# Grove_-_Optical_Rotary_Encoder_TCUT1600X.net
KiCad netlist of a schematic drawn in EAGLE
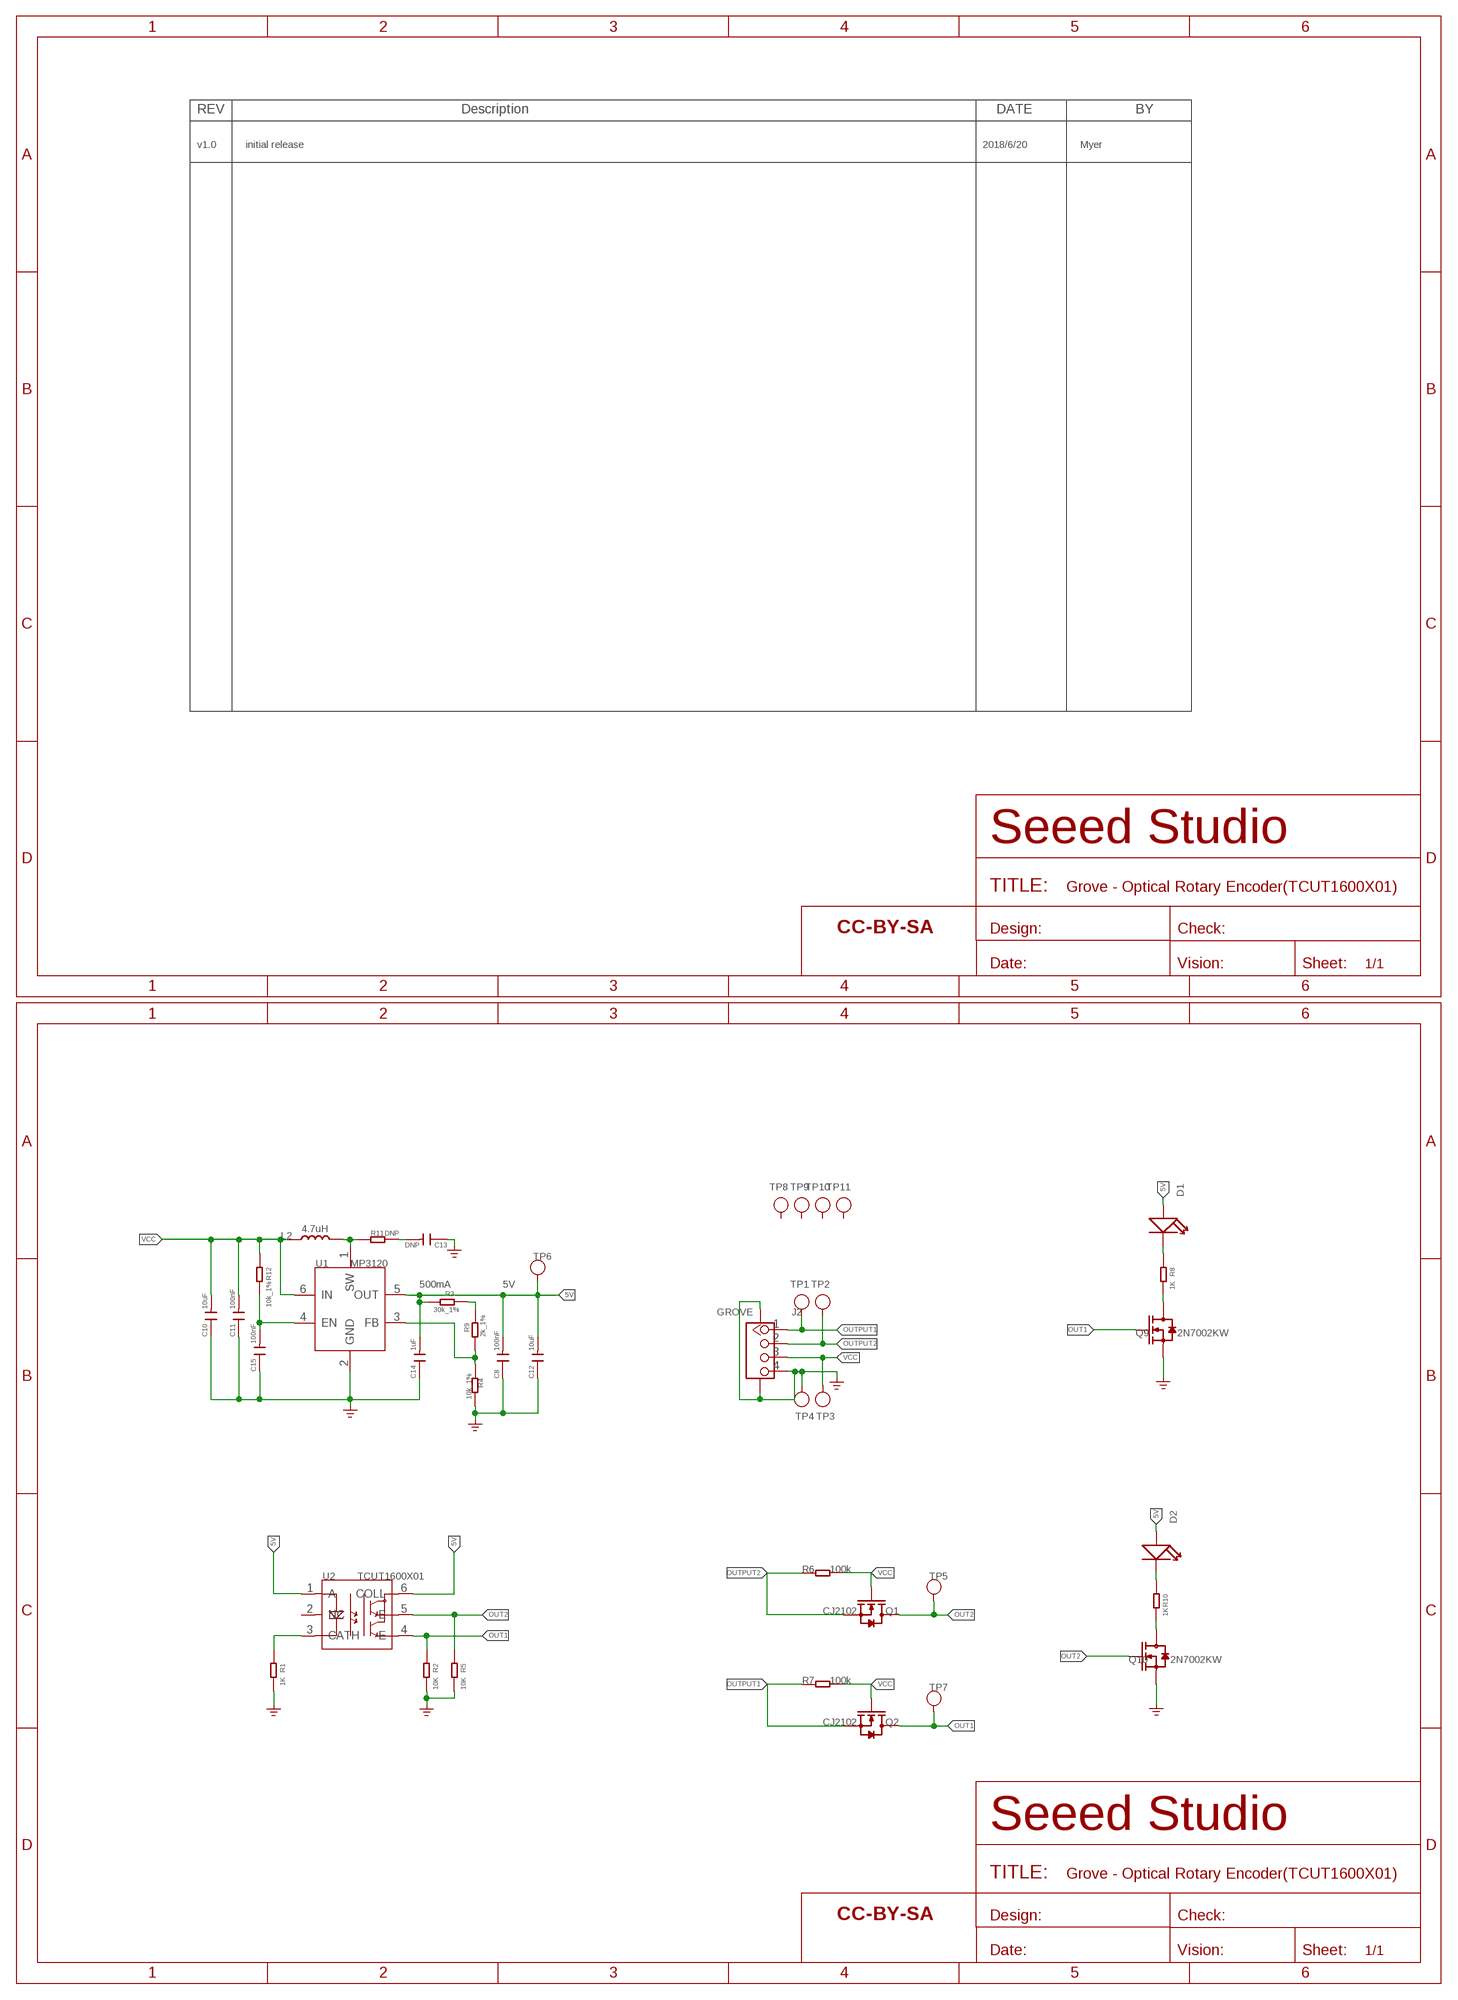
[diagram p0: schematic, sheet 1]

(export (version "E")
  (design (tool "Eeschema 10.0.6"))
  (components
    (comp (ref "C8")
      (value "100nF")
      (footprint "eagle-import:C0603")
      (libsource (lib "eagle-import") (part "C-0603"))
    )
    (comp (ref "C10")
      (value "10uF")
      (footprint "eagle-import:C0603")
      (libsource (lib "eagle-import") (part "C-0603"))
    )
    (comp (ref "C11")
      (value "100nF")
      (footprint "eagle-import:C0603")
      (libsource (lib "eagle-import") (part "C-0603"))
    )
    (comp (ref "C12")
      (value "10uF")
      (footprint "eagle-import:C0603")
      (libsource (lib "eagle-import") (part "C-0603"))
    )
    (comp (ref "C13")
      (value "DNP")
      (footprint "eagle-import:C0603")
      (libsource (lib "eagle-import") (part "C-0603"))
    )
    (comp (ref "C14")
      (value "1uF")
      (footprint "eagle-import:C0603")
      (libsource (lib "eagle-import") (part "C-0603"))
    )
    (comp (ref "C15")
      (value "100nF")
      (footprint "eagle-import:C0603")
      (libsource (lib "eagle-import") (part "C-0603"))
    )
    (comp (ref "D1")
      (value "LED'0603'")
      (footprint "eagle-import:LED-0603")
      (libsource (lib "eagle-import") (part "LED'0603'"))
    )
    (comp (ref "D2")
      (value "LED'0603'")
      (footprint "eagle-import:LED-0603")
      (libsource (lib "eagle-import") (part "LED'0603'"))
    )
    (comp (ref "FR1")
      (value "SEEEDSTUDIO-OPEN-SCH-FRAME")
      (footprint "eagle-import:SEEEDSTUDIO-PCB-FRAME")
      (libsource (lib "eagle-import") (part "SEEEDSTUDIO-OPEN-SCH-FRAME"))
    )
    (comp (ref "J2")
      (value "GROVE")
      (footprint "eagle-import:HW4-SMD-2.0")
      (libsource (lib "eagle-import") (part "GROVE-CONNECTOR-SMD'DD'"))
    )
    (comp (ref "L2")
      (value "4.7uH")
      (footprint "eagle-import:L2016")
      (libsource (lib "eagle-import") (part "LL2016"))
    )
    (comp (ref "Q1")
      (value "CJ2102")
      (footprint "eagle-import:SOT-23@1")
      (libsource (lib "eagle-import") (part "MOSFET-N'SOT23'"))
    )
    (comp (ref "Q2")
      (value "CJ2102")
      (footprint "eagle-import:SOT-23@1")
      (libsource (lib "eagle-import") (part "MOSFET-N'SOT23'"))
    )
    (comp (ref "Q9")
      (value "2N7002KW")
      (footprint "eagle-import:SOT-323")
      (libsource (lib "eagle-import") (part "MOSFET-N+'SI1304BDL'"))
    )
    (comp (ref "Q10")
      (value "2N7002KW")
      (footprint "eagle-import:SOT-323")
      (libsource (lib "eagle-import") (part "MOSFET-N+'SI1304BDL'"))
    )
    (comp (ref "R1")
      (value "1K")
      (footprint "eagle-import:R0603")
      (libsource (lib "eagle-import") (part "R-0603"))
    )
    (comp (ref "R2")
      (value "10K")
      (footprint "eagle-import:R0603")
      (libsource (lib "eagle-import") (part "R-0603"))
    )
    (comp (ref "R3")
      (value "30k_1%")
      (footprint "eagle-import:R0603")
      (libsource (lib "eagle-import") (part "R-0603"))
    )
    (comp (ref "R4")
      (value "10k_1%")
      (footprint "eagle-import:R0603")
      (libsource (lib "eagle-import") (part "R-0603"))
    )
    (comp (ref "R5")
      (value "10K")
      (footprint "eagle-import:R0603")
      (libsource (lib "eagle-import") (part "R-0603"))
    )
    (comp (ref "R6")
      (value "100k")
      (footprint "eagle-import:R0603")
      (libsource (lib "eagle-import") (part "R-0603"))
    )
    (comp (ref "R7")
      (value "100k")
      (footprint "eagle-import:R0603")
      (libsource (lib "eagle-import") (part "R-0603"))
    )
    (comp (ref "R8")
      (value "1K")
      (footprint "eagle-import:R0603")
      (libsource (lib "eagle-import") (part "R-0603"))
    )
    (comp (ref "R9")
      (value "2k_1%")
      (footprint "eagle-import:R0603")
      (libsource (lib "eagle-import") (part "R-0603"))
    )
    (comp (ref "R10")
      (value "1K")
      (footprint "eagle-import:R0603")
      (libsource (lib "eagle-import") (part "R-0603"))
    )
    (comp (ref "R11")
      (value "DNP")
      (footprint "eagle-import:R0603")
      (libsource (lib "eagle-import") (part "R-0603"))
    )
    (comp (ref "R12")
      (value "10k_1%")
      (footprint "eagle-import:R0603")
      (libsource (lib "eagle-import") (part "R-0603"))
    )
    (comp (ref "TP1")
      (value "TEST-POINT'4545'")
      (footprint "eagle-import:TP-D45MIL")
      (fields (field (name "PARTNO") "DNP"))
      (libsource (lib "eagle-import") (part "TEST-POINT'4545'"))
    )
    (comp (ref "TP2")
      (value "TEST-POINT'4545'")
      (footprint "eagle-import:TP-D45MIL")
      (fields (field (name "PARTNO") "DNP"))
      (libsource (lib "eagle-import") (part "TEST-POINT'4545'"))
    )
    (comp (ref "TP3")
      (value "TEST-POINT'4545'")
      (footprint "eagle-import:TP-D45MIL")
      (fields (field (name "PARTNO") "DNP"))
      (libsource (lib "eagle-import") (part "TEST-POINT'4545'"))
    )
    (comp (ref "TP4")
      (value "TEST-POINT'4545'")
      (footprint "eagle-import:TP-D45MIL")
      (fields (field (name "PARTNO") "DNP"))
      (libsource (lib "eagle-import") (part "TEST-POINT'4545'"))
    )
    (comp (ref "TP5")
      (value "TEST-POINT'4545'")
      (footprint "eagle-import:TP-D45MIL")
      (fields (field (name "PARTNO") "DNP"))
      (libsource (lib "eagle-import") (part "TEST-POINT'4545'"))
    )
    (comp (ref "TP6")
      (value "TEST-POINT'4545'")
      (footprint "eagle-import:TP-D45MIL")
      (fields (field (name "PARTNO") "DNP"))
      (libsource (lib "eagle-import") (part "TEST-POINT'4545'"))
    )
    (comp (ref "TP7")
      (value "TEST-POINT'4545'")
      (footprint "eagle-import:TP-D45MIL")
      (fields (field (name "PARTNO") "DNP"))
      (libsource (lib "eagle-import") (part "TEST-POINT'4545'"))
    )
    (comp (ref "TP8")
      (value "TEST-POINT'4545'")
      (footprint "eagle-import:TP-D45MIL")
      (fields (field (name "PARTNO") "DNP"))
      (libsource (lib "eagle-import") (part "TEST-POINT'4545'"))
    )
    (comp (ref "TP9")
      (value "TEST-POINT'4545'")
      (footprint "eagle-import:TP-D45MIL")
      (fields (field (name "PARTNO") "DNP"))
      (libsource (lib "eagle-import") (part "TEST-POINT'4545'"))
    )
    (comp (ref "TP10")
      (value "TEST-POINT'4545'")
      (footprint "eagle-import:TP-D45MIL")
      (fields (field (name "PARTNO") "DNP"))
      (libsource (lib "eagle-import") (part "TEST-POINT'4545'"))
    )
    (comp (ref "TP11")
      (value "TEST-POINT'4545'")
      (footprint "eagle-import:TP-D45MIL")
      (fields (field (name "PARTNO") "DNP"))
      (libsource (lib "eagle-import") (part "TEST-POINT'4545'"))
    )
    (comp (ref "U$4")
      (value "SEEEDSTUDIO-OPEN-SCH-FRAME")
      (footprint "eagle-import:SEEEDSTUDIO-PCB-FRAME")
      (libsource (lib "eagle-import") (part "SEEEDSTUDIO-OPEN-SCH-FRAME"))
    )
    (comp (ref "U1")
      (value "MP3120")
      (footprint "eagle-import:SOT-23-6")
      (libsource (lib "eagle-import") (part "CONVERTER-MP3120"))
    )
    (comp (ref "U2")
      (value "TCUT1600X01")
      (footprint "eagle-import:SNR6-1.4-5.5X4X5.7MM")
      (libsource (lib "eagle-import") (part "SENSOR-OPTICAL-TCUT1600X01"))
    )
  )
  (nets
    (net (code "1") (name "5V") (class "Default")
      (node (ref "C12") (pin "2") (pinfunction "2_2") (pintype "passive"))
      (node (ref "C14") (pin "2") (pinfunction "2_2") (pintype "passive"))
      (node (ref "C8") (pin "2") (pinfunction "2_2") (pintype "passive"))
      (node (ref "D1") (pin "+") (pinfunction "+_+") (pintype "passive"))
      (node (ref "D2") (pin "+") (pinfunction "+_+") (pintype "passive"))
      (node (ref "R3") (pin "2") (pinfunction "2_2") (pintype "passive"))
      (node (ref "TP6") (pin "T") (pinfunction "T_T") (pintype "bidirectional"))
      (node (ref "U1") (pin "5") (pinfunction "OUT_5") (pintype "bidirectional"))
      (node (ref "U2") (pin "1") (pinfunction "A_1") (pintype "bidirectional"))
      (node (ref "U2") (pin "6") (pinfunction "COLL_6") (pintype "bidirectional"))
    )
    (net (code "2") (name "GND_POWER") (class "Default")
      (node (ref "C10") (pin "1") (pinfunction "1_1") (pintype "passive"))
      (node (ref "C11") (pin "1") (pinfunction "1_1") (pintype "passive"))
      (node (ref "C12") (pin "1") (pinfunction "1_1") (pintype "passive"))
      (node (ref "C13") (pin "1") (pinfunction "1_1") (pintype "passive"))
      (node (ref "C14") (pin "1") (pinfunction "1_1") (pintype "passive"))
      (node (ref "C15") (pin "1") (pinfunction "1_1") (pintype "passive"))
      (node (ref "C8") (pin "1") (pinfunction "1_1") (pintype "passive"))
      (node (ref "J2") (pin "4") (pinfunction "4_4") (pintype "bidirectional"))
      (node (ref "J2") (pin "SS1") (pinfunction "SS1_SS1") (pintype "bidirectional"))
      (node (ref "J2") (pin "SS2") (pinfunction "SS2_SS2") (pintype "bidirectional"))
      (node (ref "Q10") (pin "2") (pinfunction "S_2") (pintype "passive"))
      (node (ref "Q9") (pin "2") (pinfunction "S_2") (pintype "passive"))
      (node (ref "R1") (pin "2") (pinfunction "2_2") (pintype "passive"))
      (node (ref "R2") (pin "2") (pinfunction "2_2") (pintype "passive"))
      (node (ref "R4") (pin "1") (pinfunction "1_1") (pintype "passive"))
      (node (ref "R5") (pin "2") (pinfunction "2_2") (pintype "passive"))
      (node (ref "TP4") (pin "T") (pinfunction "T_T") (pintype "bidirectional"))
      (node (ref "U1") (pin "2") (pinfunction "GND_2") (pintype "bidirectional"))
    )
    (net (code "3") (name "Net-(C13-Pad2)") (class "Default")
      (node (ref "C13") (pin "2") (pinfunction "2_2") (pintype "passive"))
      (node (ref "R11") (pin "2") (pinfunction "2_2") (pintype "passive"))
    )
    (net (code "4") (name "Net-(D1-Pad-)") (class "Default")
      (node (ref "D1") (pin "-") (pinfunction "-_-") (pintype "passive"))
      (node (ref "R8") (pin "1") (pinfunction "1_1") (pintype "passive"))
    )
    (net (code "5") (name "Net-(D2-Pad-)") (class "Default")
      (node (ref "D2") (pin "-") (pinfunction "-_-") (pintype "passive"))
      (node (ref "R10") (pin "1") (pinfunction "1_1") (pintype "passive"))
    )
    (net (code "6") (name "Net-(Q9-D)") (class "Default")
      (node (ref "Q9") (pin "3") (pinfunction "D_3") (pintype "passive"))
      (node (ref "R8") (pin "2") (pinfunction "2_2") (pintype "passive"))
    )
    (net (code "7") (name "Net-(Q10-D)") (class "Default")
      (node (ref "Q10") (pin "3") (pinfunction "D_3") (pintype "passive"))
      (node (ref "R10") (pin "2") (pinfunction "2_2") (pintype "passive"))
    )
    (net (code "8") (name "Net-(R3-Pad1)") (class "Default")
      (node (ref "R3") (pin "1") (pinfunction "1_1") (pintype "passive"))
      (node (ref "R9") (pin "1") (pinfunction "1_1") (pintype "passive"))
    )
    (net (code "9") (name "Net-(U1-EN)") (class "Default")
      (node (ref "C15") (pin "2") (pinfunction "2_2") (pintype "passive"))
      (node (ref "R12") (pin "2") (pinfunction "2_2") (pintype "passive"))
      (node (ref "U1") (pin "4") (pinfunction "EN_4") (pintype "bidirectional"))
    )
    (net (code "10") (name "Net-(U1-FB)") (class "Default")
      (node (ref "R4") (pin "2") (pinfunction "2_2") (pintype "passive"))
      (node (ref "R9") (pin "2") (pinfunction "2_2") (pintype "passive"))
      (node (ref "U1") (pin "3") (pinfunction "FB_3") (pintype "bidirectional"))
    )
    (net (code "11") (name "Net-(U1-SW)") (class "Default")
      (node (ref "L2") (pin "2") (pinfunction "2_2") (pintype "passive"))
      (node (ref "R11") (pin "1") (pinfunction "1_1") (pintype "passive"))
      (node (ref "U1") (pin "1") (pinfunction "SW_1") (pintype "bidirectional"))
    )
    (net (code "12") (name "Net-(U2-CATH)") (class "Default")
      (node (ref "R1") (pin "1") (pinfunction "1_1") (pintype "passive"))
      (node (ref "U2") (pin "3") (pinfunction "CATH_3") (pintype "bidirectional"))
    )
    (net (code "13") (name "OUT1") (class "Default")
      (node (ref "Q2") (pin "3") (pinfunction "D_3") (pintype "passive"))
      (node (ref "Q9") (pin "1") (pinfunction "G_1") (pintype "passive"))
      (node (ref "R2") (pin "1") (pinfunction "1_1") (pintype "passive"))
      (node (ref "TP7") (pin "T") (pinfunction "T_T") (pintype "bidirectional"))
      (node (ref "U2") (pin "4") (pinfunction "E_4") (pintype "bidirectional"))
    )
    (net (code "14") (name "OUT2") (class "Default")
      (node (ref "Q1") (pin "3") (pinfunction "D_3") (pintype "passive"))
      (node (ref "Q10") (pin "1") (pinfunction "G_1") (pintype "passive"))
      (node (ref "R5") (pin "1") (pinfunction "1_1") (pintype "passive"))
      (node (ref "TP5") (pin "T") (pinfunction "T_T") (pintype "bidirectional"))
      (node (ref "U2") (pin "5") (pinfunction "E_5") (pintype "bidirectional"))
    )
    (net (code "15") (name "OUTPUT1") (class "Default")
      (node (ref "J2") (pin "1") (pinfunction "1_1") (pintype "bidirectional"))
      (node (ref "Q2") (pin "2") (pinfunction "S_2") (pintype "passive"))
      (node (ref "R7") (pin "1") (pinfunction "1_1") (pintype "passive"))
      (node (ref "TP1") (pin "T") (pinfunction "T_T") (pintype "bidirectional"))
    )
    (net (code "16") (name "OUTPUT2") (class "Default")
      (node (ref "J2") (pin "2") (pinfunction "2_2") (pintype "bidirectional"))
      (node (ref "Q1") (pin "2") (pinfunction "S_2") (pintype "passive"))
      (node (ref "R6") (pin "1") (pinfunction "1_1") (pintype "passive"))
      (node (ref "TP2") (pin "T") (pinfunction "T_T") (pintype "bidirectional"))
    )
    (net (code "17") (name "VCC") (class "Default")
      (node (ref "C10") (pin "2") (pinfunction "2_2") (pintype "passive"))
      (node (ref "C11") (pin "2") (pinfunction "2_2") (pintype "passive"))
      (node (ref "J2") (pin "3") (pinfunction "3_3") (pintype "bidirectional"))
      (node (ref "L2") (pin "1") (pinfunction "1_1") (pintype "passive"))
      (node (ref "Q1") (pin "1") (pinfunction "G_1") (pintype "passive"))
      (node (ref "Q2") (pin "1") (pinfunction "G_1") (pintype "passive"))
      (node (ref "R12") (pin "1") (pinfunction "1_1") (pintype "passive"))
      (node (ref "R6") (pin "2") (pinfunction "2_2") (pintype "passive"))
      (node (ref "R7") (pin "2") (pinfunction "2_2") (pintype "passive"))
      (node (ref "TP3") (pin "T") (pinfunction "T_T") (pintype "bidirectional"))
      (node (ref "U1") (pin "6") (pinfunction "IN_6") (pintype "bidirectional"))
    )
    (net (code "18") (name "unconnected-(TP8-PadT)") (class "Default")
      (node (ref "TP8") (pin "T") (pinfunction "T_T") (pintype "bidirectional"))
    )
    (net (code "19") (name "unconnected-(TP9-PadT)") (class "Default")
      (node (ref "TP9") (pin "T") (pinfunction "T_T") (pintype "bidirectional"))
    )
    (net (code "20") (name "unconnected-(TP10-PadT)") (class "Default")
      (node (ref "TP10") (pin "T") (pinfunction "T_T") (pintype "bidirectional"))
    )
    (net (code "21") (name "unconnected-(TP11-PadT)") (class "Default")
      (node (ref "TP11") (pin "T") (pinfunction "T_T") (pintype "bidirectional"))
    )
    (net (code "22") (name "unconnected-(U2-NC-Pad2)") (class "Default")
      (node (ref "U2") (pin "2") (pinfunction "NC_2") (pintype "bidirectional"))
    )
  )
)
